# FPGA_Power.net
KiCad netlist of a schematic drawn in Altium Designer
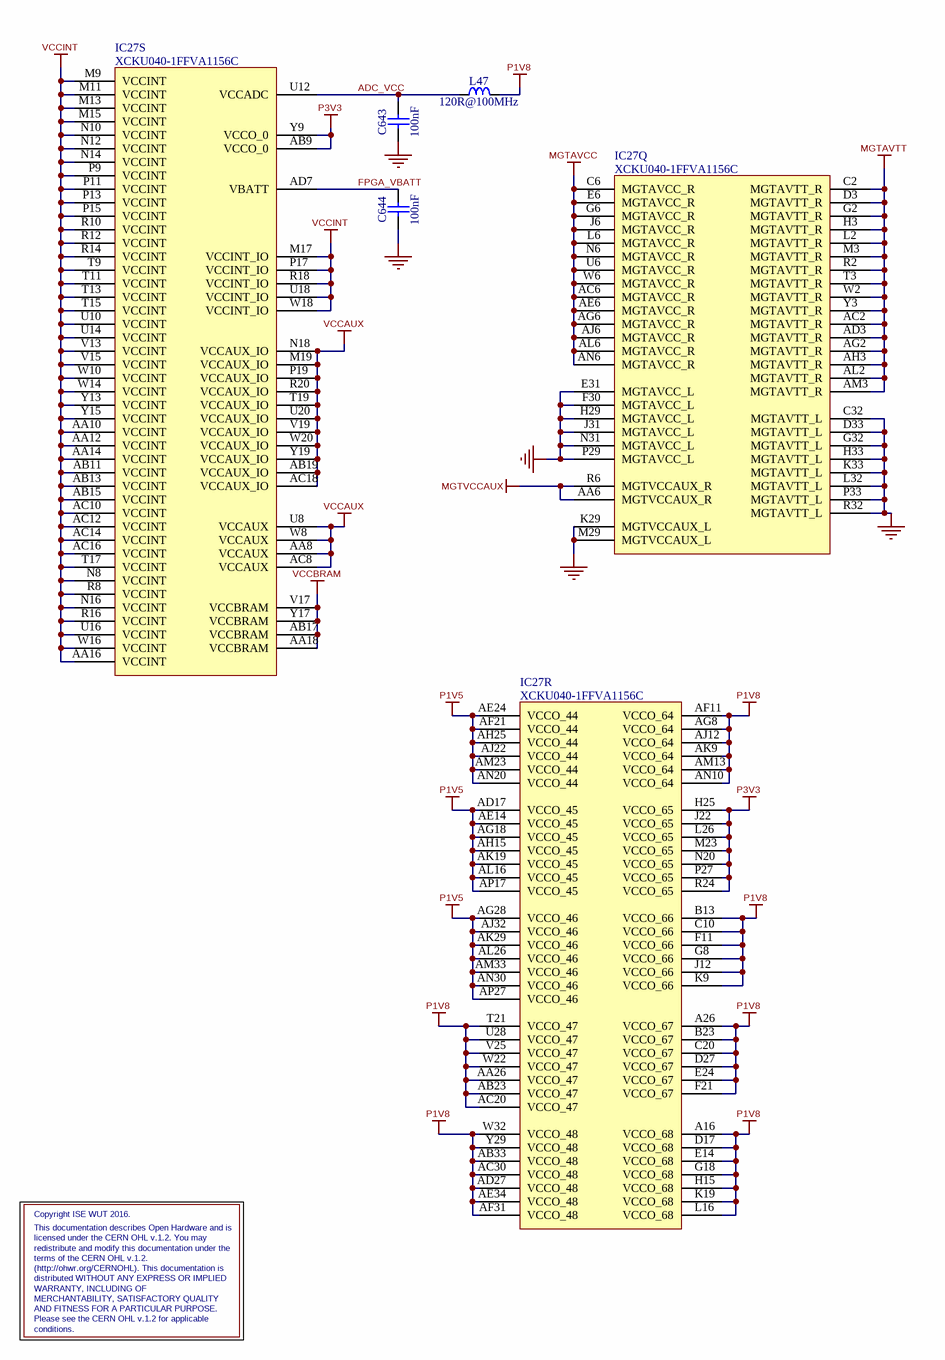
[diagram p0: FPGA_Power.SchDoc]

(export (version "E")
  (design (tool "Eeschema 10.0.6"))
  (components
    (comp (ref "C643")
      (value "100nF")
      (footprint "CAPC0603X33N")
      (description "Non-polarised capacitor")
      (fields
        (field (name "MANUFACTURER PART NUMBER") "CC0201_100NF_6.3V_10%_X5R")
        (field (name "MANUFACTURER") "GENERIC")
        (field (name "AUTHOR") "CERN DEM JLC")
      )
      (libsource (lib "Capacitors") (part "Capacitor - non polarized"))
    )
    (comp (ref "C644")
      (value "100nF")
      (footprint "CAPC0603X33N")
      (description "Non-polarised capacitor")
      (fields
        (field (name "MANUFACTURER PART NUMBER") "CC0201_100NF_6.3V_10%_X5R")
        (field (name "MANUFACTURER") "GENERIC")
        (field (name "AUTHOR") "CERN DEM JLC")
      )
      (libsource (lib "Capacitors") (part "Capacitor - non polarized"))
    )
    (comp (ref "IC27")
      (value "XCKU040-1FFVA1156C")
      (footprint "BGA1156C100P34X34_3500X3500X350")
      (description "Kintex UltraScale FPGA, 520 I/O, 530K Cells, 1156-Ball BGA, Speed Grade 1, Commercial Grade")
      (fields (field (name "MANUFACTURER") "XILINX") (field (name "AUTHOR") "CERN DEM CA"))
      (libsource (lib "ICs And Semiconductors") (part "XCKU040-1FFVA1156C"))
    )
    (comp (ref "L47")
      (value "120R@100MHz")
      (footprint "INDC1005X55N")
      (description "Inductor")
      (fields
        (field (name "MANUFACTURER PART NUMBER") "BLM15PX121SN1D")
        (field (name "MANUFACTURER") "MURATA")
        (field (name "AUTHOR") "CERN DEM JMW")
      )
      (libsource (lib "Inductors & Transformers") (part "Inductor"))
    )
  )
  (nets
    (net (code "1") (name "/ADC_VCC") (class "Default")
      (node (ref "C643") (pin "2") (pinfunction "2_2") (pintype "passive"))
      (node (ref "IC27") (pin "U12") (pinfunction "VCCADC_U12") (pintype "power_in"))
      (node (ref "L47") (pin "1") (pinfunction "1_1") (pintype "passive"))
    )
    (net (code "2") (name "/FPGA_VBATT") (class "Default")
      (node (ref "C644") (pin "2") (pinfunction "2_2") (pintype "passive"))
      (node (ref "IC27") (pin "AD7") (pinfunction "VBATT_AD7") (pintype "power_in"))
    )
    (net (code "3") (name "GND") (class "Default")
      (node (ref "C643") (pin "1") (pinfunction "1_1") (pintype "passive"))
      (node (ref "C644") (pin "1") (pinfunction "1_1") (pintype "passive"))
      (node (ref "IC27") (pin "C32") (pinfunction "MGTAVTT_L_C32") (pintype "power_in"))
      (node (ref "IC27") (pin "D33") (pinfunction "MGTAVTT_L_D33") (pintype "power_in"))
      (node (ref "IC27") (pin "E31") (pinfunction "MGTAVCC_L_E31") (pintype "power_in"))
      (node (ref "IC27") (pin "F30") (pinfunction "MGTAVCC_L_F30") (pintype "power_in"))
      (node (ref "IC27") (pin "G32") (pinfunction "MGTAVTT_L_G32") (pintype "power_in"))
      (node (ref "IC27") (pin "H29") (pinfunction "MGTAVCC_L_H29") (pintype "power_in"))
      (node (ref "IC27") (pin "H33") (pinfunction "MGTAVTT_L_H33") (pintype "power_in"))
      (node (ref "IC27") (pin "J31") (pinfunction "MGTAVCC_L_J31") (pintype "power_in"))
      (node (ref "IC27") (pin "K29") (pinfunction "MGTVCCAUX_L_K29") (pintype "power_in"))
      (node (ref "IC27") (pin "K33") (pinfunction "MGTAVTT_L_K33") (pintype "power_in"))
      (node (ref "IC27") (pin "L32") (pinfunction "MGTAVTT_L_L32") (pintype "power_in"))
      (node (ref "IC27") (pin "M29") (pinfunction "MGTVCCAUX_L_M29") (pintype "power_in"))
      (node (ref "IC27") (pin "N31") (pinfunction "MGTAVCC_L_N31") (pintype "power_in"))
      (node (ref "IC27") (pin "P29") (pinfunction "MGTAVCC_L_P29") (pintype "power_in"))
      (node (ref "IC27") (pin "P33") (pinfunction "MGTAVTT_L_P33") (pintype "power_in"))
      (node (ref "IC27") (pin "R32") (pinfunction "MGTAVTT_L_R32") (pintype "power_in"))
    )
    (net (code "4") (name "MGTAVCC") (class "Default")
      (node (ref "IC27") (pin "AC6") (pinfunction "MGTAVCC_R_AC6") (pintype "power_in"))
      (node (ref "IC27") (pin "AE6") (pinfunction "MGTAVCC_R_AE6") (pintype "power_in"))
      (node (ref "IC27") (pin "AG6") (pinfunction "MGTAVCC_R_AG6") (pintype "power_in"))
      (node (ref "IC27") (pin "AJ6") (pinfunction "MGTAVCC_R_AJ6") (pintype "power_in"))
      (node (ref "IC27") (pin "AL6") (pinfunction "MGTAVCC_R_AL6") (pintype "power_in"))
      (node (ref "IC27") (pin "AN6") (pinfunction "MGTAVCC_R_AN6") (pintype "power_in"))
      (node (ref "IC27") (pin "C6") (pinfunction "MGTAVCC_R_C6") (pintype "power_in"))
      (node (ref "IC27") (pin "E6") (pinfunction "MGTAVCC_R_E6") (pintype "power_in"))
      (node (ref "IC27") (pin "G6") (pinfunction "MGTAVCC_R_G6") (pintype "power_in"))
      (node (ref "IC27") (pin "J6") (pinfunction "MGTAVCC_R_J6") (pintype "power_in"))
      (node (ref "IC27") (pin "L6") (pinfunction "MGTAVCC_R_L6") (pintype "power_in"))
      (node (ref "IC27") (pin "N6") (pinfunction "MGTAVCC_R_N6") (pintype "power_in"))
      (node (ref "IC27") (pin "U6") (pinfunction "MGTAVCC_R_U6") (pintype "power_in"))
      (node (ref "IC27") (pin "W6") (pinfunction "MGTAVCC_R_W6") (pintype "power_in"))
    )
    (net (code "5") (name "MGTAVTT") (class "Default")
      (node (ref "IC27") (pin "AC2") (pinfunction "MGTAVTT_R_AC2") (pintype "power_in"))
      (node (ref "IC27") (pin "AD3") (pinfunction "MGTAVTT_R_AD3") (pintype "power_in"))
      (node (ref "IC27") (pin "AG2") (pinfunction "MGTAVTT_R_AG2") (pintype "power_in"))
      (node (ref "IC27") (pin "AH3") (pinfunction "MGTAVTT_R_AH3") (pintype "power_in"))
      (node (ref "IC27") (pin "AL2") (pinfunction "MGTAVTT_R_AL2") (pintype "power_in"))
      (node (ref "IC27") (pin "AM3") (pinfunction "MGTAVTT_R_AM3") (pintype "power_in"))
      (node (ref "IC27") (pin "C2") (pinfunction "MGTAVTT_R_C2") (pintype "power_in"))
      (node (ref "IC27") (pin "D3") (pinfunction "MGTAVTT_R_D3") (pintype "power_in"))
      (node (ref "IC27") (pin "G2") (pinfunction "MGTAVTT_R_G2") (pintype "power_in"))
      (node (ref "IC27") (pin "H3") (pinfunction "MGTAVTT_R_H3") (pintype "power_in"))
      (node (ref "IC27") (pin "L2") (pinfunction "MGTAVTT_R_L2") (pintype "power_in"))
      (node (ref "IC27") (pin "M3") (pinfunction "MGTAVTT_R_M3") (pintype "power_in"))
      (node (ref "IC27") (pin "R2") (pinfunction "MGTAVTT_R_R2") (pintype "power_in"))
      (node (ref "IC27") (pin "T3") (pinfunction "MGTAVTT_R_T3") (pintype "power_in"))
      (node (ref "IC27") (pin "W2") (pinfunction "MGTAVTT_R_W2") (pintype "power_in"))
      (node (ref "IC27") (pin "Y3") (pinfunction "MGTAVTT_R_Y3") (pintype "power_in"))
    )
    (net (code "6") (name "MGTVCCAUX") (class "Default")
      (node (ref "IC27") (pin "AA6") (pinfunction "MGTVCCAUX_R_AA6") (pintype "power_in"))
      (node (ref "IC27") (pin "R6") (pinfunction "MGTVCCAUX_R_R6") (pintype "power_in"))
    )
    (net (code "7") (name "P1V5") (class "Default")
      (node (ref "IC27") (pin "AD17") (pinfunction "VCCO_45_AD17") (pintype "power_in"))
      (node (ref "IC27") (pin "AE14") (pinfunction "VCCO_45_AE14") (pintype "power_in"))
      (node (ref "IC27") (pin "AE24") (pinfunction "VCCO_44_AE24") (pintype "power_in"))
      (node (ref "IC27") (pin "AF21") (pinfunction "VCCO_44_AF21") (pintype "power_in"))
      (node (ref "IC27") (pin "AG18") (pinfunction "VCCO_45_AG18") (pintype "power_in"))
      (node (ref "IC27") (pin "AG28") (pinfunction "VCCO_46_AG28") (pintype "power_in"))
      (node (ref "IC27") (pin "AH15") (pinfunction "VCCO_45_AH15") (pintype "power_in"))
      (node (ref "IC27") (pin "AH25") (pinfunction "VCCO_44_AH25") (pintype "power_in"))
      (node (ref "IC27") (pin "AJ22") (pinfunction "VCCO_44_AJ22") (pintype "power_in"))
      (node (ref "IC27") (pin "AJ32") (pinfunction "VCCO_46_AJ32") (pintype "power_in"))
      (node (ref "IC27") (pin "AK19") (pinfunction "VCCO_45_AK19") (pintype "power_in"))
      (node (ref "IC27") (pin "AK29") (pinfunction "VCCO_46_AK29") (pintype "power_in"))
      (node (ref "IC27") (pin "AL16") (pinfunction "VCCO_45_AL16") (pintype "power_in"))
      (node (ref "IC27") (pin "AL26") (pinfunction "VCCO_46_AL26") (pintype "power_in"))
      (node (ref "IC27") (pin "AM23") (pinfunction "VCCO_44_AM23") (pintype "power_in"))
      (node (ref "IC27") (pin "AM33") (pinfunction "VCCO_46_AM33") (pintype "power_in"))
      (node (ref "IC27") (pin "AN20") (pinfunction "VCCO_44_AN20") (pintype "power_in"))
      (node (ref "IC27") (pin "AN30") (pinfunction "VCCO_46_AN30") (pintype "power_in"))
      (node (ref "IC27") (pin "AP17") (pinfunction "VCCO_45_AP17") (pintype "power_in"))
      (node (ref "IC27") (pin "AP27") (pinfunction "VCCO_46_AP27") (pintype "power_in"))
    )
    (net (code "8") (name "P1V8") (class "Default")
      (node (ref "IC27") (pin "A16") (pinfunction "VCCO_68_A16") (pintype "power_in"))
      (node (ref "IC27") (pin "A26") (pinfunction "VCCO_67_A26") (pintype "power_in"))
      (node (ref "IC27") (pin "AA26") (pinfunction "VCCO_47_AA26") (pintype "power_in"))
      (node (ref "IC27") (pin "AB23") (pinfunction "VCCO_47_AB23") (pintype "power_in"))
      (node (ref "IC27") (pin "AB33") (pinfunction "VCCO_48_AB33") (pintype "power_in"))
      (node (ref "IC27") (pin "AC20") (pinfunction "VCCO_47_AC20") (pintype "power_in"))
      (node (ref "IC27") (pin "AC30") (pinfunction "VCCO_48_AC30") (pintype "power_in"))
      (node (ref "IC27") (pin "AD27") (pinfunction "VCCO_48_AD27") (pintype "power_in"))
      (node (ref "IC27") (pin "AE34") (pinfunction "VCCO_48_AE34") (pintype "power_in"))
      (node (ref "IC27") (pin "AF11") (pinfunction "VCCO_64_AF11") (pintype "power_in"))
      (node (ref "IC27") (pin "AF31") (pinfunction "VCCO_48_AF31") (pintype "power_in"))
      (node (ref "IC27") (pin "AG8") (pinfunction "VCCO_64_AG8") (pintype "power_in"))
      (node (ref "IC27") (pin "AJ12") (pinfunction "VCCO_64_AJ12") (pintype "power_in"))
      (node (ref "IC27") (pin "AK9") (pinfunction "VCCO_64_AK9") (pintype "power_in"))
      (node (ref "IC27") (pin "AM13") (pinfunction "VCCO_64_AM13") (pintype "power_in"))
      (node (ref "IC27") (pin "AN10") (pinfunction "VCCO_64_AN10") (pintype "power_in"))
      (node (ref "IC27") (pin "B13") (pinfunction "VCCO_66_B13") (pintype "power_in"))
      (node (ref "IC27") (pin "B23") (pinfunction "VCCO_67_B23") (pintype "power_in"))
      (node (ref "IC27") (pin "C10") (pinfunction "VCCO_66_C10") (pintype "power_in"))
      (node (ref "IC27") (pin "C20") (pinfunction "VCCO_67_C20") (pintype "power_in"))
      (node (ref "IC27") (pin "D17") (pinfunction "VCCO_68_D17") (pintype "power_in"))
      (node (ref "IC27") (pin "D27") (pinfunction "VCCO_67_D27") (pintype "power_in"))
      (node (ref "IC27") (pin "E14") (pinfunction "VCCO_68_E14") (pintype "power_in"))
      (node (ref "IC27") (pin "E24") (pinfunction "VCCO_67_E24") (pintype "power_in"))
      (node (ref "IC27") (pin "F11") (pinfunction "VCCO_66_F11") (pintype "power_in"))
      (node (ref "IC27") (pin "F21") (pinfunction "VCCO_67_F21") (pintype "power_in"))
      (node (ref "IC27") (pin "G18") (pinfunction "VCCO_68_G18") (pintype "power_in"))
      (node (ref "IC27") (pin "G8") (pinfunction "VCCO_66_G8") (pintype "power_in"))
      (node (ref "IC27") (pin "H15") (pinfunction "VCCO_68_H15") (pintype "power_in"))
      (node (ref "IC27") (pin "J12") (pinfunction "VCCO_66_J12") (pintype "power_in"))
      (node (ref "IC27") (pin "K19") (pinfunction "VCCO_68_K19") (pintype "power_in"))
      (node (ref "IC27") (pin "K9") (pinfunction "VCCO_66_K9") (pintype "power_in"))
      (node (ref "IC27") (pin "L16") (pinfunction "VCCO_68_L16") (pintype "power_in"))
      (node (ref "IC27") (pin "T21") (pinfunction "VCCO_47_T21") (pintype "power_in"))
      (node (ref "IC27") (pin "U28") (pinfunction "VCCO_47_U28") (pintype "power_in"))
      (node (ref "IC27") (pin "V25") (pinfunction "VCCO_47_V25") (pintype "power_in"))
      (node (ref "IC27") (pin "W22") (pinfunction "VCCO_47_W22") (pintype "power_in"))
      (node (ref "IC27") (pin "W32") (pinfunction "VCCO_48_W32") (pintype "power_in"))
      (node (ref "IC27") (pin "Y29") (pinfunction "VCCO_48_Y29") (pintype "power_in"))
      (node (ref "L47") (pin "2") (pinfunction "2_2") (pintype "passive"))
    )
    (net (code "9") (name "P3V3") (class "Default")
      (node (ref "IC27") (pin "AB9") (pinfunction "VCCO_0_AB9") (pintype "power_in"))
      (node (ref "IC27") (pin "H25") (pinfunction "VCCO_65_H25") (pintype "power_in"))
      (node (ref "IC27") (pin "J22") (pinfunction "VCCO_65_J22") (pintype "power_in"))
      (node (ref "IC27") (pin "L26") (pinfunction "VCCO_65_L26") (pintype "power_in"))
      (node (ref "IC27") (pin "M23") (pinfunction "VCCO_65_M23") (pintype "power_in"))
      (node (ref "IC27") (pin "N20") (pinfunction "VCCO_65_N20") (pintype "power_in"))
      (node (ref "IC27") (pin "P27") (pinfunction "VCCO_65_P27") (pintype "power_in"))
      (node (ref "IC27") (pin "R24") (pinfunction "VCCO_65_R24") (pintype "power_in"))
      (node (ref "IC27") (pin "Y9") (pinfunction "VCCO_0_Y9") (pintype "power_in"))
    )
    (net (code "10") (name "VCCAUX") (class "Default")
      (node (ref "IC27") (pin "AA8") (pinfunction "VCCAUX_AA8") (pintype "power_in"))
      (node (ref "IC27") (pin "AB19") (pinfunction "VCCAUX_IO_AB19") (pintype "power_in"))
      (node (ref "IC27") (pin "AC18") (pinfunction "VCCAUX_IO_AC18") (pintype "power_in"))
      (node (ref "IC27") (pin "AC8") (pinfunction "VCCAUX_AC8") (pintype "power_in"))
      (node (ref "IC27") (pin "M19") (pinfunction "VCCAUX_IO_M19") (pintype "power_in"))
      (node (ref "IC27") (pin "N18") (pinfunction "VCCAUX_IO_N18") (pintype "power_in"))
      (node (ref "IC27") (pin "P19") (pinfunction "VCCAUX_IO_P19") (pintype "power_in"))
      (node (ref "IC27") (pin "R20") (pinfunction "VCCAUX_IO_R20") (pintype "power_in"))
      (node (ref "IC27") (pin "T19") (pinfunction "VCCAUX_IO_T19") (pintype "power_in"))
      (node (ref "IC27") (pin "U20") (pinfunction "VCCAUX_IO_U20") (pintype "power_in"))
      (node (ref "IC27") (pin "U8") (pinfunction "VCCAUX_U8") (pintype "power_in"))
      (node (ref "IC27") (pin "V19") (pinfunction "VCCAUX_IO_V19") (pintype "power_in"))
      (node (ref "IC27") (pin "W20") (pinfunction "VCCAUX_IO_W20") (pintype "power_in"))
      (node (ref "IC27") (pin "W8") (pinfunction "VCCAUX_W8") (pintype "power_in"))
      (node (ref "IC27") (pin "Y19") (pinfunction "VCCAUX_IO_Y19") (pintype "power_in"))
    )
    (net (code "11") (name "VCCBRAM") (class "Default")
      (node (ref "IC27") (pin "AA18") (pinfunction "VCCBRAM_AA18") (pintype "power_in"))
      (node (ref "IC27") (pin "AB17") (pinfunction "VCCBRAM_AB17") (pintype "power_in"))
      (node (ref "IC27") (pin "V17") (pinfunction "VCCBRAM_V17") (pintype "power_in"))
      (node (ref "IC27") (pin "Y17") (pinfunction "VCCBRAM_Y17") (pintype "power_in"))
    )
    (net (code "12") (name "VCCINT") (class "Default")
      (node (ref "IC27") (pin "AA10") (pinfunction "VCCINT_AA10") (pintype "power_in"))
      (node (ref "IC27") (pin "AA12") (pinfunction "VCCINT_AA12") (pintype "power_in"))
      (node (ref "IC27") (pin "AA14") (pinfunction "VCCINT_AA14") (pintype "power_in"))
      (node (ref "IC27") (pin "AA16") (pinfunction "VCCINT_AA16") (pintype "power_in"))
      (node (ref "IC27") (pin "AB11") (pinfunction "VCCINT_AB11") (pintype "power_in"))
      (node (ref "IC27") (pin "AB13") (pinfunction "VCCINT_AB13") (pintype "power_in"))
      (node (ref "IC27") (pin "AB15") (pinfunction "VCCINT_AB15") (pintype "power_in"))
      (node (ref "IC27") (pin "AC10") (pinfunction "VCCINT_AC10") (pintype "power_in"))
      (node (ref "IC27") (pin "AC12") (pinfunction "VCCINT_AC12") (pintype "power_in"))
      (node (ref "IC27") (pin "AC14") (pinfunction "VCCINT_AC14") (pintype "power_in"))
      (node (ref "IC27") (pin "AC16") (pinfunction "VCCINT_AC16") (pintype "power_in"))
      (node (ref "IC27") (pin "M11") (pinfunction "VCCINT_M11") (pintype "power_in"))
      (node (ref "IC27") (pin "M13") (pinfunction "VCCINT_M13") (pintype "power_in"))
      (node (ref "IC27") (pin "M15") (pinfunction "VCCINT_M15") (pintype "power_in"))
      (node (ref "IC27") (pin "M17") (pinfunction "VCCINT_IO_M17") (pintype "power_in"))
      (node (ref "IC27") (pin "M9") (pinfunction "VCCINT_M9") (pintype "power_in"))
      (node (ref "IC27") (pin "N10") (pinfunction "VCCINT_N10") (pintype "power_in"))
      (node (ref "IC27") (pin "N12") (pinfunction "VCCINT_N12") (pintype "power_in"))
      (node (ref "IC27") (pin "N14") (pinfunction "VCCINT_N14") (pintype "power_in"))
      (node (ref "IC27") (pin "N16") (pinfunction "VCCINT_N16") (pintype "power_in"))
      (node (ref "IC27") (pin "N8") (pinfunction "VCCINT_N8") (pintype "power_in"))
      (node (ref "IC27") (pin "P11") (pinfunction "VCCINT_P11") (pintype "power_in"))
      (node (ref "IC27") (pin "P13") (pinfunction "VCCINT_P13") (pintype "power_in"))
      (node (ref "IC27") (pin "P15") (pinfunction "VCCINT_P15") (pintype "power_in"))
      (node (ref "IC27") (pin "P17") (pinfunction "VCCINT_IO_P17") (pintype "power_in"))
      (node (ref "IC27") (pin "P9") (pinfunction "VCCINT_P9") (pintype "power_in"))
      (node (ref "IC27") (pin "R10") (pinfunction "VCCINT_R10") (pintype "power_in"))
      (node (ref "IC27") (pin "R12") (pinfunction "VCCINT_R12") (pintype "power_in"))
      (node (ref "IC27") (pin "R14") (pinfunction "VCCINT_R14") (pintype "power_in"))
      (node (ref "IC27") (pin "R16") (pinfunction "VCCINT_R16") (pintype "power_in"))
      (node (ref "IC27") (pin "R18") (pinfunction "VCCINT_IO_R18") (pintype "power_in"))
      (node (ref "IC27") (pin "R8") (pinfunction "VCCINT_R8") (pintype "power_in"))
      (node (ref "IC27") (pin "T11") (pinfunction "VCCINT_T11") (pintype "power_in"))
      (node (ref "IC27") (pin "T13") (pinfunction "VCCINT_T13") (pintype "power_in"))
      (node (ref "IC27") (pin "T15") (pinfunction "VCCINT_T15") (pintype "power_in"))
      (node (ref "IC27") (pin "T17") (pinfunction "VCCINT_T17") (pintype "power_in"))
      (node (ref "IC27") (pin "T9") (pinfunction "VCCINT_T9") (pintype "power_in"))
      (node (ref "IC27") (pin "U10") (pinfunction "VCCINT_U10") (pintype "power_in"))
      (node (ref "IC27") (pin "U14") (pinfunction "VCCINT_U14") (pintype "power_in"))
      (node (ref "IC27") (pin "U16") (pinfunction "VCCINT_U16") (pintype "power_in"))
      (node (ref "IC27") (pin "U18") (pinfunction "VCCINT_IO_U18") (pintype "power_in"))
      (node (ref "IC27") (pin "V13") (pinfunction "VCCINT_V13") (pintype "power_in"))
      (node (ref "IC27") (pin "V15") (pinfunction "VCCINT_V15") (pintype "power_in"))
      (node (ref "IC27") (pin "W10") (pinfunction "VCCINT_W10") (pintype "power_in"))
      (node (ref "IC27") (pin "W14") (pinfunction "VCCINT_W14") (pintype "power_in"))
      (node (ref "IC27") (pin "W16") (pinfunction "VCCINT_W16") (pintype "power_in"))
      (node (ref "IC27") (pin "W18") (pinfunction "VCCINT_IO_W18") (pintype "power_in"))
      (node (ref "IC27") (pin "Y13") (pinfunction "VCCINT_Y13") (pintype "power_in"))
      (node (ref "IC27") (pin "Y15") (pinfunction "VCCINT_Y15") (pintype "power_in"))
    )
  )
)
